# Ampel.net
KiCad netlist of a schematic drawn in EAGLE
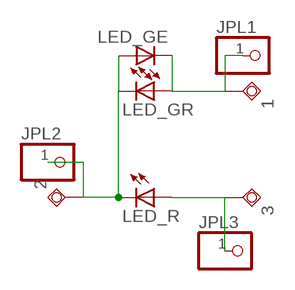
[diagram p0: schematic, sheet 1]

(export (version "E")
  (design (tool "Eeschema 10.0.6"))
  (components
    (comp (ref "1")
      (value "1")
      (footprint "eagle-import:TP10SQ")
      (libsource (lib "eagle-import") (part "TPSQTP10SQ"))
    )
    (comp (ref "2")
      (value "2")
      (footprint "eagle-import:TP10SQ")
      (libsource (lib "eagle-import") (part "TPSQTP10SQ"))
    )
    (comp (ref "3")
      (value "3")
      (footprint "eagle-import:TP10SQ")
      (libsource (lib "eagle-import") (part "TPSQTP10SQ"))
    )
    (comp (ref "JPL1")
      (value "PINHD-1X1KL")
      (footprint "eagle-import:1X01_KL")
      (libsource (lib "eagle-import") (part "PINHD-1X1KL"))
    )
    (comp (ref "JPL2")
      (value "PINHD-1X1KL")
      (footprint "eagle-import:1X01_KL")
      (libsource (lib "eagle-import") (part "PINHD-1X1KL"))
    )
    (comp (ref "JPL3")
      (value "PINHD-1X1KL")
      (footprint "eagle-import:1X01_KL")
      (libsource (lib "eagle-import") (part "PINHD-1X1KL"))
    )
    (comp (ref "LED_GE")
      (value "LEDCHIP_-LED0402")
      (footprint "eagle-import:CHIP-LED0402")
      (libsource (lib "eagle-import") (part "LEDCHIP_-LED0402"))
    )
    (comp (ref "LED_GR")
      (value "LEDCHIP_-LED0402")
      (footprint "eagle-import:CHIP-LED0402")
      (libsource (lib "eagle-import") (part "LEDCHIP_-LED0402"))
    )
    (comp (ref "LED_R")
      (value "LEDCHIP_-LED0402")
      (footprint "eagle-import:CHIP-LED0402")
      (libsource (lib "eagle-import") (part "LEDCHIP_-LED0402"))
    )
  )
  (nets
    (net (code "1") (name "Net-(1-PadTP)") (class "Default")
      (node (ref "1") (pin "TP") (pinfunction "TP_TP") (pintype "input"))
      (node (ref "JPL1") (pin "1") (pinfunction "1_1") (pintype "passive"))
      (node (ref "LED_GE") (pin "C") (pinfunction "C_C") (pintype "passive"))
      (node (ref "LED_GR") (pin "A") (pinfunction "A_A") (pintype "passive"))
    )
    (net (code "2") (name "Net-(2-PadTP)") (class "Default")
      (node (ref "2") (pin "TP") (pinfunction "TP_TP") (pintype "input"))
      (node (ref "JPL2") (pin "1") (pinfunction "1_1") (pintype "passive"))
      (node (ref "LED_GE") (pin "A") (pinfunction "A_A") (pintype "passive"))
      (node (ref "LED_GR") (pin "C") (pinfunction "C_C") (pintype "passive"))
      (node (ref "LED_R") (pin "C") (pinfunction "C_C") (pintype "passive"))
    )
    (net (code "3") (name "Net-(3-PadTP)") (class "Default")
      (node (ref "3") (pin "TP") (pinfunction "TP_TP") (pintype "input"))
      (node (ref "JPL3") (pin "1") (pinfunction "1_1") (pintype "passive"))
      (node (ref "LED_R") (pin "A") (pinfunction "A_A") (pintype "passive"))
    )
  )
)
